# Ace81_build04.net
KiCad netlist of a schematic drawn in EAGLE
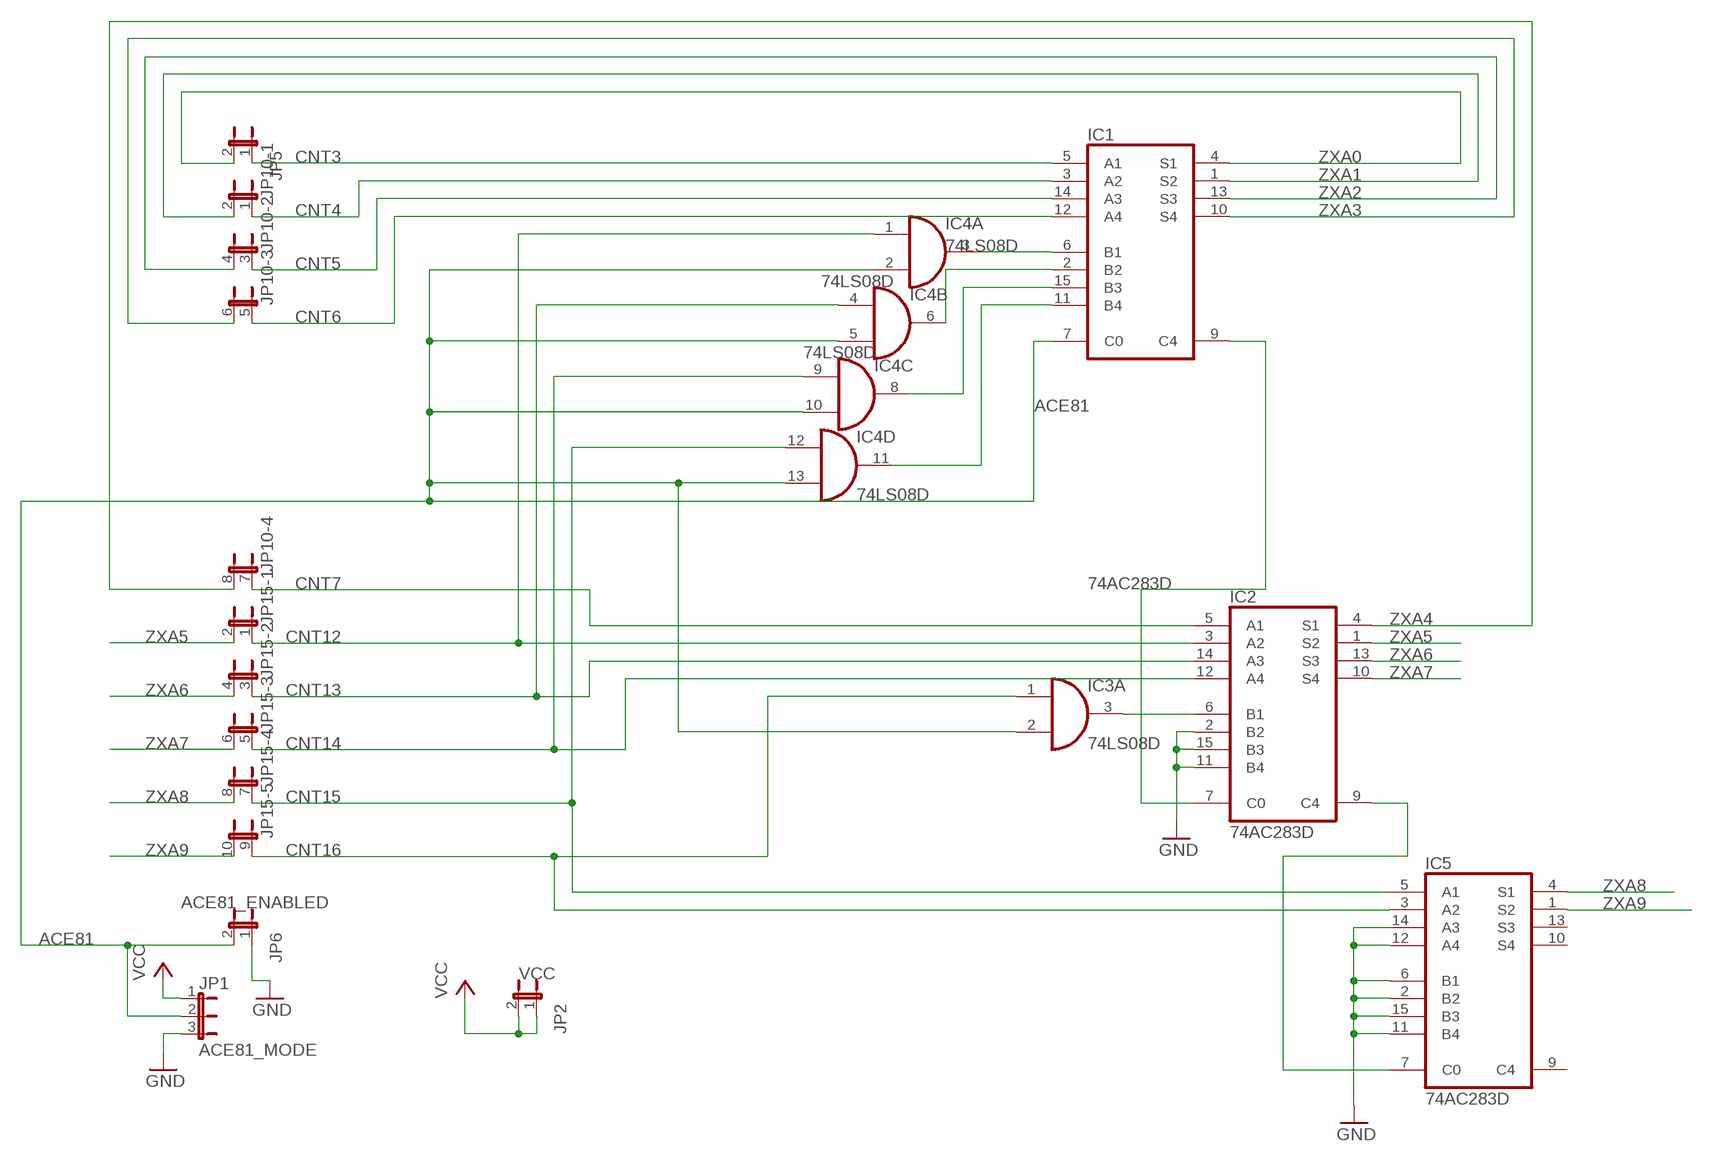
[diagram p0: schematic, sheet 1]

(export (version "E")
  (design (tool "Eeschema 10.0.6"))
  (components
    (comp (ref "IC1")
      (value "74AC283D")
      (footprint "eagle-import:SO16")
      (libsource (lib "eagle-import") (part "74283DAC"))
    )
    (comp (ref "IC2")
      (value "74AC283D")
      (footprint "eagle-import:SO16")
      (libsource (lib "eagle-import") (part "74283DAC"))
    )
    (comp (ref "IC3")
      (value "74LS08D")
      (footprint "eagle-import:SO14")
      (libsource (lib "eagle-import") (part "7408DLS"))
    )
    (comp (ref "IC4")
      (value "74LS08D")
      (footprint "eagle-import:SO14")
      (libsource (lib "eagle-import") (part "7408DLS"))
    )
    (comp (ref "IC5")
      (value "74AC283D")
      (footprint "eagle-import:SO16")
      (libsource (lib "eagle-import") (part "74283DAC"))
    )
    (comp (ref "JP1")
      (value "ACE81_MODE")
      (footprint "eagle-import:JP2")
      (libsource (lib "eagle-import") (part "JP2E"))
    )
    (comp (ref "JP2")
      (value "VCC")
      (footprint "eagle-import:JP1Q")
      (libsource (lib "eagle-import") (part "JP1E1Q"))
    )
    (comp (ref "JP5")
      (value "JP1E1Q")
      (footprint "eagle-import:JP1Q")
      (libsource (lib "eagle-import") (part "JP1E1Q"))
    )
    (comp (ref "JP6")
      (value "ACE81_ENABLED")
      (footprint "eagle-import:JP1Q")
      (libsource (lib "eagle-import") (part "JP1E1Q"))
    )
    (comp (ref "JP10")
      (value "JP4QE")
      (footprint "eagle-import:JP4Q")
      (libsource (lib "eagle-import") (part "JP4QE"))
    )
    (comp (ref "JP15")
      (value "JP5QE")
      (footprint "eagle-import:JP5Q")
      (libsource (lib "eagle-import") (part "JP5QE"))
    )
  )
  (nets
    (net (code "1") (name "/ACE81") (class "Default")
      (node (ref "IC1") (pin "7") (pinfunction "C0_7") (pintype "input"))
      (node (ref "IC3") (pin "2") (pinfunction "I1_2") (pintype "input"))
      (node (ref "IC4") (pin "10") (pinfunction "I1_10") (pintype "input"))
      (node (ref "IC4") (pin "13") (pinfunction "I1_13") (pintype "input"))
      (node (ref "IC4") (pin "2") (pinfunction "I1_2") (pintype "input"))
      (node (ref "IC4") (pin "5") (pinfunction "I1_5") (pintype "input"))
      (node (ref "JP1") (pin "2") (pinfunction "2_2") (pintype "passive"))
      (node (ref "JP6") (pin "2") (pinfunction "2_2") (pintype "passive"))
    )
    (net (code "2") (name "/CNT3") (class "Default")
      (node (ref "IC1") (pin "5") (pinfunction "A1_5") (pintype "input"))
      (node (ref "JP5") (pin "1") (pinfunction "1_1") (pintype "passive"))
    )
    (net (code "3") (name "/CNT4") (class "Default")
      (node (ref "IC1") (pin "3") (pinfunction "A2_3") (pintype "input"))
      (node (ref "JP10") (pin "1") (pinfunction "1_1") (pintype "passive"))
    )
    (net (code "4") (name "/CNT5") (class "Default")
      (node (ref "IC1") (pin "14") (pinfunction "A3_14") (pintype "input"))
      (node (ref "JP10") (pin "3") (pinfunction "1_3") (pintype "passive"))
    )
    (net (code "5") (name "/CNT6") (class "Default")
      (node (ref "IC1") (pin "12") (pinfunction "A4_12") (pintype "input"))
      (node (ref "JP10") (pin "5") (pinfunction "1_5") (pintype "passive"))
    )
    (net (code "6") (name "/CNT7") (class "Default")
      (node (ref "IC2") (pin "5") (pinfunction "A1_5") (pintype "input"))
      (node (ref "JP10") (pin "7") (pinfunction "1_7") (pintype "passive"))
    )
    (net (code "7") (name "/CNT12") (class "Default")
      (node (ref "IC2") (pin "3") (pinfunction "A2_3") (pintype "input"))
      (node (ref "IC4") (pin "1") (pinfunction "I0_1") (pintype "input"))
      (node (ref "JP15") (pin "1") (pinfunction "1_1") (pintype "passive"))
    )
    (net (code "8") (name "/CNT13") (class "Default")
      (node (ref "IC2") (pin "14") (pinfunction "A3_14") (pintype "input"))
      (node (ref "IC4") (pin "4") (pinfunction "I0_4") (pintype "input"))
      (node (ref "JP15") (pin "3") (pinfunction "1_3") (pintype "passive"))
    )
    (net (code "9") (name "/CNT14") (class "Default")
      (node (ref "IC2") (pin "12") (pinfunction "A4_12") (pintype "input"))
      (node (ref "IC4") (pin "9") (pinfunction "I0_9") (pintype "input"))
      (node (ref "JP15") (pin "5") (pinfunction "1_5") (pintype "passive"))
    )
    (net (code "10") (name "/CNT15") (class "Default")
      (node (ref "IC4") (pin "12") (pinfunction "I0_12") (pintype "input"))
      (node (ref "IC5") (pin "5") (pinfunction "A1_5") (pintype "input"))
      (node (ref "JP15") (pin "7") (pinfunction "1_7") (pintype "passive"))
    )
    (net (code "11") (name "/CNT16") (class "Default")
      (node (ref "IC3") (pin "1") (pinfunction "I0_1") (pintype "input"))
      (node (ref "IC5") (pin "3") (pinfunction "A2_3") (pintype "input"))
      (node (ref "JP15") (pin "9") (pinfunction "1_9") (pintype "passive"))
    )
    (net (code "12") (name "/ZXA0") (class "Default")
      (node (ref "IC1") (pin "4") (pinfunction "S1_4") (pintype "output"))
      (node (ref "JP5") (pin "2") (pinfunction "2_2") (pintype "passive"))
    )
    (net (code "13") (name "/ZXA1") (class "Default")
      (node (ref "IC1") (pin "1") (pinfunction "S2_1") (pintype "output"))
      (node (ref "JP10") (pin "2") (pinfunction "2_2") (pintype "passive"))
    )
    (net (code "14") (name "/ZXA2") (class "Default")
      (node (ref "IC1") (pin "13") (pinfunction "S3_13") (pintype "output"))
      (node (ref "JP10") (pin "4") (pinfunction "2_4") (pintype "passive"))
    )
    (net (code "15") (name "/ZXA3") (class "Default")
      (node (ref "IC1") (pin "10") (pinfunction "S4_10") (pintype "output"))
      (node (ref "JP10") (pin "6") (pinfunction "2_6") (pintype "passive"))
    )
    (net (code "16") (name "/ZXA4") (class "Default")
      (node (ref "IC2") (pin "4") (pinfunction "S1_4") (pintype "output"))
      (node (ref "JP10") (pin "8") (pinfunction "2_8") (pintype "passive"))
    )
    (net (code "17") (name "/ZXA5") (class "Default")
      (node (ref "IC2") (pin "1") (pinfunction "S2_1") (pintype "output"))
      (node (ref "JP15") (pin "2") (pinfunction "2_2") (pintype "passive"))
    )
    (net (code "18") (name "/ZXA6") (class "Default")
      (node (ref "IC2") (pin "13") (pinfunction "S3_13") (pintype "output"))
      (node (ref "JP15") (pin "4") (pinfunction "2_4") (pintype "passive"))
    )
    (net (code "19") (name "/ZXA7") (class "Default")
      (node (ref "IC2") (pin "10") (pinfunction "S4_10") (pintype "output"))
      (node (ref "JP15") (pin "6") (pinfunction "2_6") (pintype "passive"))
    )
    (net (code "20") (name "/ZXA8") (class "Default")
      (node (ref "IC5") (pin "4") (pinfunction "S1_4") (pintype "output"))
      (node (ref "JP15") (pin "8") (pinfunction "2_8") (pintype "passive"))
    )
    (net (code "21") (name "/ZXA9") (class "Default")
      (node (ref "IC5") (pin "1") (pinfunction "S2_1") (pintype "output"))
      (node (ref "JP15") (pin "10") (pinfunction "2_10") (pintype "passive"))
    )
    (net (code "22") (name "GND") (class "Default")
      (node (ref "IC2") (pin "11") (pinfunction "B4_11") (pintype "input"))
      (node (ref "IC2") (pin "15") (pinfunction "B3_15") (pintype "input"))
      (node (ref "IC2") (pin "2") (pinfunction "B2_2") (pintype "input"))
      (node (ref "IC5") (pin "11") (pinfunction "B4_11") (pintype "input"))
      (node (ref "IC5") (pin "12") (pinfunction "A4_12") (pintype "input"))
      (node (ref "IC5") (pin "14") (pinfunction "A3_14") (pintype "input"))
      (node (ref "IC5") (pin "15") (pinfunction "B3_15") (pintype "input"))
      (node (ref "IC5") (pin "2") (pinfunction "B2_2") (pintype "input"))
      (node (ref "IC5") (pin "6") (pinfunction "B1_6") (pintype "input"))
      (node (ref "JP1") (pin "3") (pinfunction "3_3") (pintype "passive"))
      (node (ref "JP6") (pin "1") (pinfunction "1_1") (pintype "passive"))
    )
    (net (code "23") (name "Net-(IC1A-B1)") (class "Default")
      (node (ref "IC1") (pin "6") (pinfunction "B1_6") (pintype "input"))
      (node (ref "IC4") (pin "3") (pinfunction "O_3") (pintype "output"))
    )
    (net (code "24") (name "Net-(IC1A-B2)") (class "Default")
      (node (ref "IC1") (pin "2") (pinfunction "B2_2") (pintype "input"))
      (node (ref "IC4") (pin "6") (pinfunction "O_6") (pintype "output"))
    )
    (net (code "25") (name "Net-(IC1A-B3)") (class "Default")
      (node (ref "IC1") (pin "15") (pinfunction "B3_15") (pintype "input"))
      (node (ref "IC4") (pin "8") (pinfunction "O_8") (pintype "output"))
    )
    (net (code "26") (name "Net-(IC1A-B4)") (class "Default")
      (node (ref "IC1") (pin "11") (pinfunction "B4_11") (pintype "input"))
      (node (ref "IC4") (pin "11") (pinfunction "O_11") (pintype "output"))
    )
    (net (code "27") (name "Net-(IC1A-C4)") (class "Default")
      (node (ref "IC1") (pin "9") (pinfunction "C4_9") (pintype "output"))
      (node (ref "IC2") (pin "7") (pinfunction "C0_7") (pintype "input"))
    )
    (net (code "28") (name "Net-(IC2A-B1)") (class "Default")
      (node (ref "IC2") (pin "6") (pinfunction "B1_6") (pintype "input"))
      (node (ref "IC3") (pin "3") (pinfunction "O_3") (pintype "output"))
    )
    (net (code "29") (name "Net-(IC2A-C4)") (class "Default")
      (node (ref "IC2") (pin "9") (pinfunction "C4_9") (pintype "output"))
      (node (ref "IC5") (pin "7") (pinfunction "C0_7") (pintype "input"))
    )
    (net (code "30") (name "VCC") (class "Default")
      (node (ref "JP1") (pin "1") (pinfunction "1_1") (pintype "passive"))
      (node (ref "JP2") (pin "1") (pinfunction "1_1") (pintype "passive"))
      (node (ref "JP2") (pin "2") (pinfunction "2_2") (pintype "passive"))
    )
    (net (code "31") (name "unconnected-(IC5A-C4-Pad9)") (class "Default")
      (node (ref "IC5") (pin "9") (pinfunction "C4_9") (pintype "output"))
    )
    (net (code "32") (name "unconnected-(IC5A-S3-Pad13)") (class "Default")
      (node (ref "IC5") (pin "13") (pinfunction "S3_13") (pintype "output"))
    )
    (net (code "33") (name "unconnected-(IC5A-S4-Pad10)") (class "Default")
      (node (ref "IC5") (pin "10") (pinfunction "S4_10") (pintype "output"))
    )
  )
)
